# rpiSensors.net
KiCad netlist of a schematic drawn in EAGLE
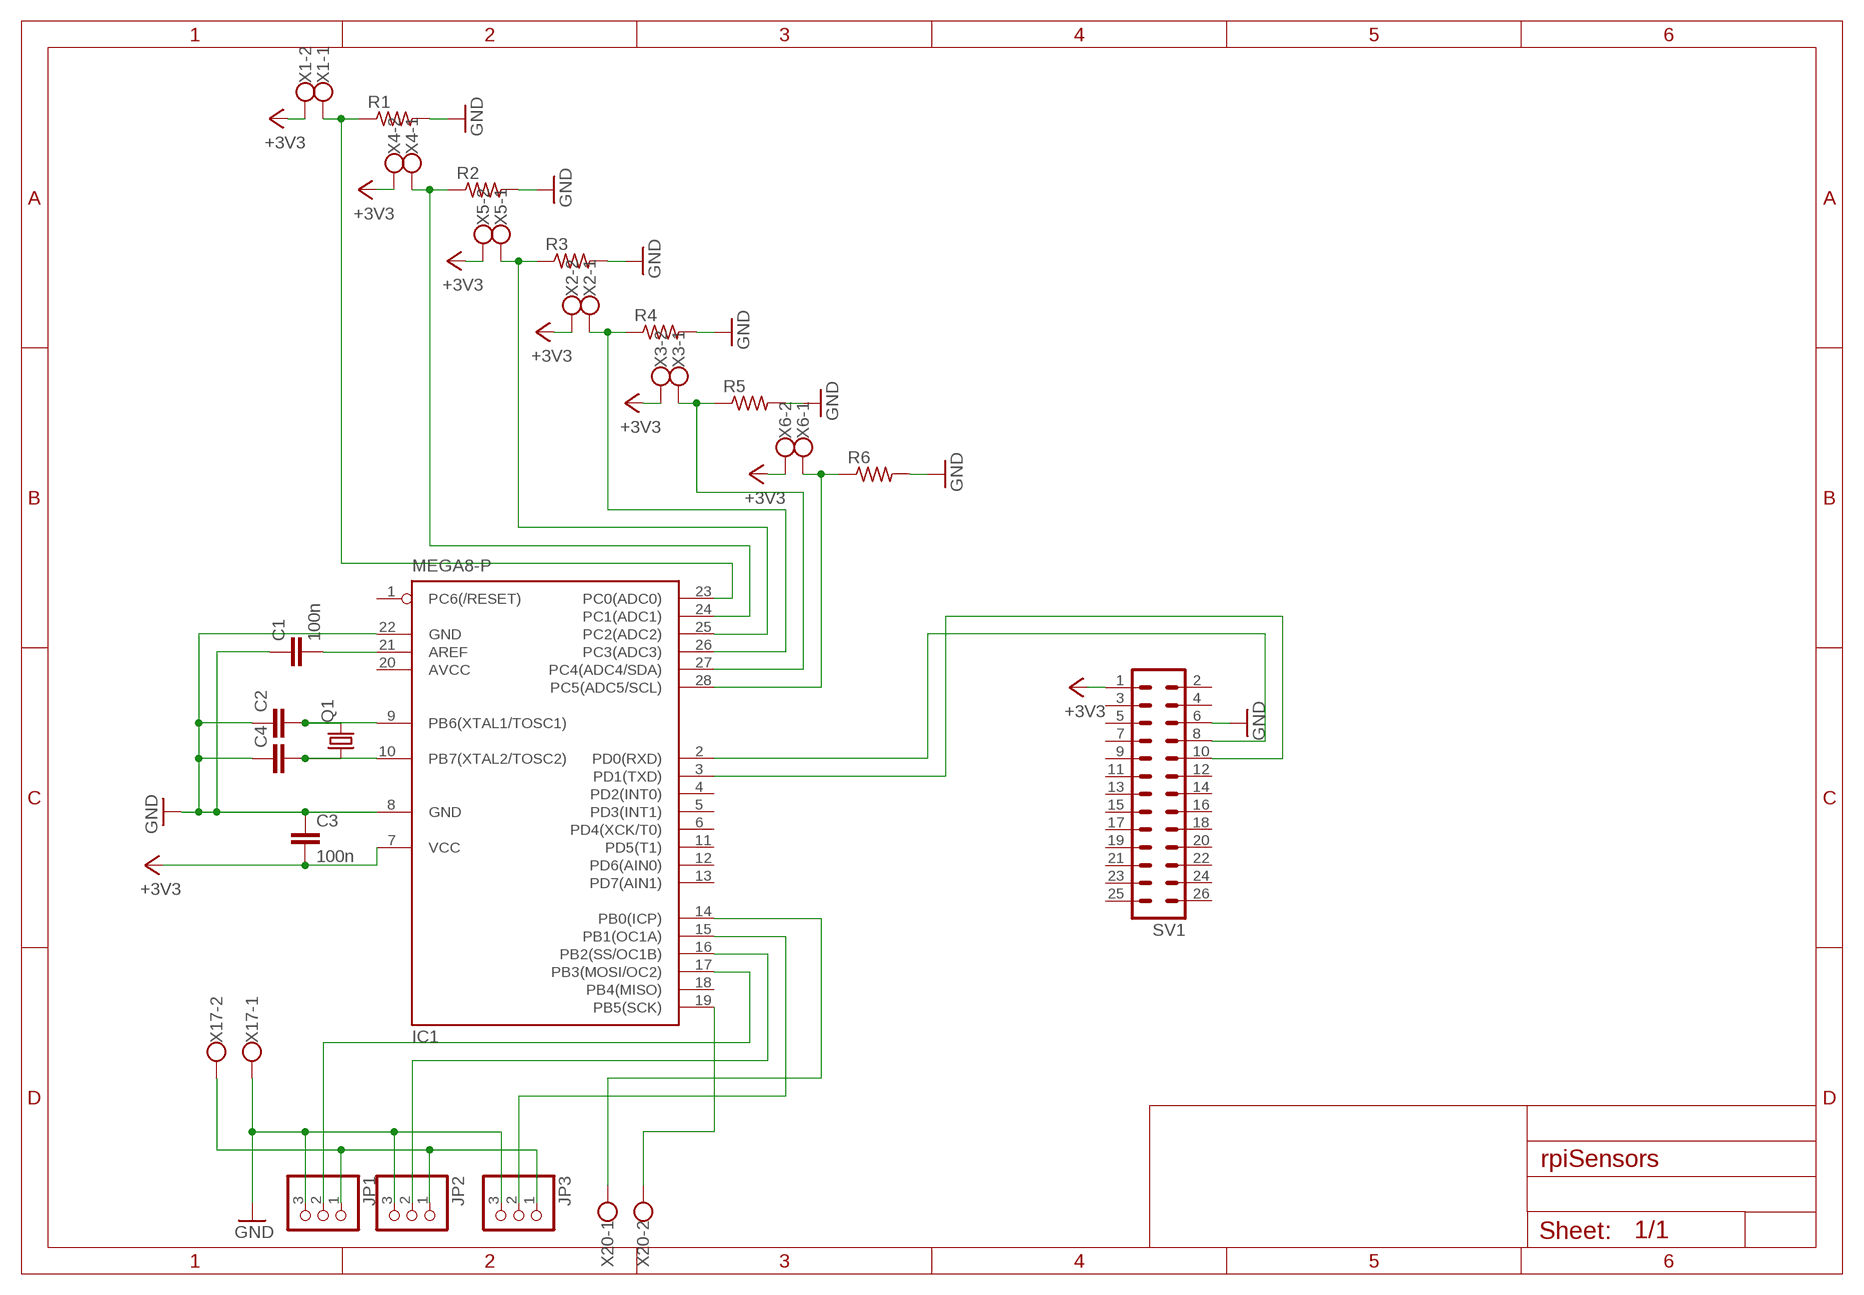
[diagram p0: schematic, sheet 1]

(export (version "E")
  (design (tool "Eeschema 10.0.6"))
  (components
    (comp (ref "C1")
      (value "100n")
      (footprint "eagle-import:C2.5-3")
      (libsource (lib "eagle-import") (part "C2,5-3"))
    )
    (comp (ref "C2")
      (value "C5/2.5")
      (footprint "eagle-import:C5B2.5")
      (libsource (lib "eagle-import") (part "C5/2.5"))
    )
    (comp (ref "C3")
      (value "100n")
      (footprint "eagle-import:C2.5-3")
      (libsource (lib "eagle-import") (part "C2,5-3"))
    )
    (comp (ref "C4")
      (value "C5/2.5")
      (footprint "eagle-import:C5B2.5")
      (libsource (lib "eagle-import") (part "C5/2.5"))
    )
    (comp (ref "IC1")
      (value "MEGA8-P")
      (footprint "eagle-import:DIL28-3")
      (libsource (lib "eagle-import") (part "MEGA8-P"))
    )
    (comp (ref "JP1")
      (value "PINHD-1X3")
      (footprint "eagle-import:1X03")
      (libsource (lib "eagle-import") (part "PINHD-1X3"))
    )
    (comp (ref "JP2")
      (value "PINHD-1X3")
      (footprint "eagle-import:1X03")
      (libsource (lib "eagle-import") (part "PINHD-1X3"))
    )
    (comp (ref "JP3")
      (value "PINHD-1X3")
      (footprint "eagle-import:1X03")
      (libsource (lib "eagle-import") (part "PINHD-1X3"))
    )
    (comp (ref "Q1")
      (value "CRYSTALHC49S")
      (footprint "eagle-import:HC49_S")
      (libsource (lib "eagle-import") (part "CRYSTALHC49S"))
    )
    (comp (ref "R1")
      (value "R-US_0309/12")
      (footprint "eagle-import:0309_12")
      (libsource (lib "eagle-import") (part "R-US_0309/12"))
    )
    (comp (ref "R2")
      (value "R-US_0309/12")
      (footprint "eagle-import:0309_12")
      (libsource (lib "eagle-import") (part "R-US_0309/12"))
    )
    (comp (ref "R3")
      (value "R-US_0309/12")
      (footprint "eagle-import:0309_12")
      (libsource (lib "eagle-import") (part "R-US_0309/12"))
    )
    (comp (ref "R4")
      (value "R-US_0309/12")
      (footprint "eagle-import:0309_12")
      (libsource (lib "eagle-import") (part "R-US_0309/12"))
    )
    (comp (ref "R5")
      (value "R-US_0309/12")
      (footprint "eagle-import:0309_12")
      (libsource (lib "eagle-import") (part "R-US_0309/12"))
    )
    (comp (ref "R6")
      (value "R-US_0309/12")
      (footprint "eagle-import:0309_12")
      (libsource (lib "eagle-import") (part "R-US_0309/12"))
    )
    (comp (ref "SV1")
      (value "ML26")
      (footprint "eagle-import:ML26")
      (libsource (lib "eagle-import") (part "ML26"))
    )
    (comp (ref "X1")
      (value "W237-102")
      (footprint "eagle-import:W237-102")
      (fields (field (name "MPN") "237-102"))
      (libsource (lib "eagle-import") (part "W237-102"))
    )
    (comp (ref "X2")
      (value "W237-102")
      (footprint "eagle-import:W237-102")
      (fields (field (name "MPN") "237-102"))
      (libsource (lib "eagle-import") (part "W237-102"))
    )
    (comp (ref "X3")
      (value "W237-102")
      (footprint "eagle-import:W237-102")
      (fields (field (name "MPN") "237-102"))
      (libsource (lib "eagle-import") (part "W237-102"))
    )
    (comp (ref "X4")
      (value "W237-102")
      (footprint "eagle-import:W237-102")
      (fields (field (name "MPN") "237-102"))
      (libsource (lib "eagle-import") (part "W237-102"))
    )
    (comp (ref "X5")
      (value "W237-102")
      (footprint "eagle-import:W237-102")
      (fields (field (name "MPN") "237-102"))
      (libsource (lib "eagle-import") (part "W237-102"))
    )
    (comp (ref "X6")
      (value "W237-102")
      (footprint "eagle-import:W237-102")
      (fields (field (name "MPN") "237-102"))
      (libsource (lib "eagle-import") (part "W237-102"))
    )
    (comp (ref "X17")
      (value "W237-102")
      (footprint "eagle-import:W237-102")
      (fields (field (name "MPN") "237-102"))
      (libsource (lib "eagle-import") (part "W237-102"))
    )
    (comp (ref "X20")
      (value "W237-102")
      (footprint "eagle-import:W237-102")
      (fields (field (name "MPN") "237-102"))
      (libsource (lib "eagle-import") (part "W237-102"))
    )
  )
  (nets
    (net (code "1") (name "+3V3") (class "Default")
      (node (ref "C3") (pin "2") (pinfunction "2_2") (pintype "passive"))
      (node (ref "IC1") (pin "7") (pinfunction "VCC_7") (pintype "power_in"))
      (node (ref "SV1") (pin "1") (pinfunction "1_1") (pintype "passive"))
      (node (ref "X1") (pin "2") (pinfunction "KL_2") (pintype "passive"))
      (node (ref "X2") (pin "2") (pinfunction "KL_2") (pintype "passive"))
      (node (ref "X3") (pin "2") (pinfunction "KL_2") (pintype "passive"))
      (node (ref "X4") (pin "2") (pinfunction "KL_2") (pintype "passive"))
      (node (ref "X5") (pin "2") (pinfunction "KL_2") (pintype "passive"))
      (node (ref "X6") (pin "2") (pinfunction "KL_2") (pintype "passive"))
    )
    (net (code "2") (name "/AVCC") (class "Default")
      (node (ref "IC1") (pin "20") (pinfunction "AVCC_20") (pintype "power_in"))
    )
    (net (code "3") (name "GND") (class "Default")
      (node (ref "C1") (pin "1") (pinfunction "1_1") (pintype "passive"))
      (node (ref "C2") (pin "1") (pinfunction "1_1") (pintype "passive"))
      (node (ref "C3") (pin "1") (pinfunction "1_1") (pintype "passive"))
      (node (ref "C4") (pin "1") (pinfunction "1_1") (pintype "passive"))
      (node (ref "IC1") (pin "22") (pinfunction "GND_22") (pintype "power_in"))
      (node (ref "IC1") (pin "8") (pinfunction "GND_8") (pintype "power_in"))
      (node (ref "JP1") (pin "3") (pinfunction "3_3") (pintype "passive"))
      (node (ref "JP2") (pin "3") (pinfunction "3_3") (pintype "passive"))
      (node (ref "JP3") (pin "3") (pinfunction "3_3") (pintype "passive"))
      (node (ref "R1") (pin "2") (pinfunction "2_2") (pintype "passive"))
      (node (ref "R2") (pin "2") (pinfunction "2_2") (pintype "passive"))
      (node (ref "R3") (pin "2") (pinfunction "2_2") (pintype "passive"))
      (node (ref "R4") (pin "2") (pinfunction "2_2") (pintype "passive"))
      (node (ref "R5") (pin "2") (pinfunction "2_2") (pintype "passive"))
      (node (ref "R6") (pin "2") (pinfunction "2_2") (pintype "passive"))
      (node (ref "SV1") (pin "6") (pinfunction "6_6") (pintype "passive"))
      (node (ref "X17") (pin "1") (pinfunction "KL_1") (pintype "passive"))
    )
    (net (code "4") (name "Net-(IC1-AREF)") (class "Default")
      (node (ref "C1") (pin "2") (pinfunction "2_2") (pintype "passive"))
      (node (ref "IC1") (pin "21") (pinfunction "AREF_21") (pintype "passive"))
    )
    (net (code "5") (name "Net-(IC1-PB0(ICP))") (class "Default")
      (node (ref "IC1") (pin "14") (pinfunction "PB0(ICP)_14") (pintype "bidirectional"))
      (node (ref "X20") (pin "1") (pinfunction "KL_1") (pintype "passive"))
    )
    (net (code "6") (name "Net-(IC1-PB1(OC1A))") (class "Default")
      (node (ref "IC1") (pin "15") (pinfunction "PB1(OC1A)_15") (pintype "bidirectional"))
      (node (ref "JP3") (pin "2") (pinfunction "2_2") (pintype "passive"))
    )
    (net (code "7") (name "Net-(IC1-PB2(SS{slash}OC1B))") (class "Default")
      (node (ref "IC1") (pin "16") (pinfunction "PB2(SS/OC1B)_16") (pintype "bidirectional"))
      (node (ref "JP2") (pin "2") (pinfunction "2_2") (pintype "passive"))
    )
    (net (code "8") (name "Net-(IC1-PB3(MOSI{slash}OC2))") (class "Default")
      (node (ref "IC1") (pin "17") (pinfunction "PB3(MOSI/OC2)_17") (pintype "bidirectional"))
      (node (ref "JP1") (pin "2") (pinfunction "2_2") (pintype "passive"))
    )
    (net (code "9") (name "Net-(IC1-PB5(SCK))") (class "Default")
      (node (ref "IC1") (pin "19") (pinfunction "PB5(SCK)_19") (pintype "bidirectional"))
      (node (ref "X20") (pin "2") (pinfunction "KL_2") (pintype "passive"))
    )
    (net (code "10") (name "Net-(IC1-PB6(XTAL1{slash}TOSC1))") (class "Default")
      (node (ref "C2") (pin "2") (pinfunction "2_2") (pintype "passive"))
      (node (ref "IC1") (pin "9") (pinfunction "PB6(XTAL1/TOSC1)_9") (pintype "bidirectional"))
      (node (ref "Q1") (pin "2") (pinfunction "2_2") (pintype "passive"))
    )
    (net (code "11") (name "Net-(IC1-PB7(XTAL2{slash}TOSC2))") (class "Default")
      (node (ref "C4") (pin "2") (pinfunction "2_2") (pintype "passive"))
      (node (ref "IC1") (pin "10") (pinfunction "PB7(XTAL2/TOSC2)_10") (pintype "bidirectional"))
      (node (ref "Q1") (pin "1") (pinfunction "1_1") (pintype "passive"))
    )
    (net (code "12") (name "Net-(IC1-PC0(ADC0))") (class "Default")
      (node (ref "IC1") (pin "23") (pinfunction "PC0(ADC0)_23") (pintype "bidirectional"))
      (node (ref "R1") (pin "1") (pinfunction "1_1") (pintype "passive"))
      (node (ref "X1") (pin "1") (pinfunction "KL_1") (pintype "passive"))
    )
    (net (code "13") (name "Net-(IC1-PC1(ADC1))") (class "Default")
      (node (ref "IC1") (pin "24") (pinfunction "PC1(ADC1)_24") (pintype "bidirectional"))
      (node (ref "R2") (pin "1") (pinfunction "1_1") (pintype "passive"))
      (node (ref "X4") (pin "1") (pinfunction "KL_1") (pintype "passive"))
    )
    (net (code "14") (name "Net-(IC1-PC2(ADC2))") (class "Default")
      (node (ref "IC1") (pin "25") (pinfunction "PC2(ADC2)_25") (pintype "bidirectional"))
      (node (ref "R3") (pin "1") (pinfunction "1_1") (pintype "passive"))
      (node (ref "X5") (pin "1") (pinfunction "KL_1") (pintype "passive"))
    )
    (net (code "15") (name "Net-(IC1-PC3(ADC3))") (class "Default")
      (node (ref "IC1") (pin "26") (pinfunction "PC3(ADC3)_26") (pintype "bidirectional"))
      (node (ref "R4") (pin "1") (pinfunction "1_1") (pintype "passive"))
      (node (ref "X2") (pin "1") (pinfunction "KL_1") (pintype "passive"))
    )
    (net (code "16") (name "Net-(IC1-PC4(ADC4{slash}SDA))") (class "Default")
      (node (ref "IC1") (pin "27") (pinfunction "PC4(ADC4/SDA)_27") (pintype "bidirectional"))
      (node (ref "R5") (pin "1") (pinfunction "1_1") (pintype "passive"))
      (node (ref "X3") (pin "1") (pinfunction "KL_1") (pintype "passive"))
    )
    (net (code "17") (name "Net-(IC1-PC5(ADC5{slash}SCL))") (class "Default")
      (node (ref "IC1") (pin "28") (pinfunction "PC5(ADC5/SCL)_28") (pintype "bidirectional"))
      (node (ref "R6") (pin "1") (pinfunction "1_1") (pintype "passive"))
      (node (ref "X6") (pin "1") (pinfunction "KL_1") (pintype "passive"))
    )
    (net (code "18") (name "Net-(IC1-PD0(RXD))") (class "Default")
      (node (ref "IC1") (pin "2") (pinfunction "PD0(RXD)_2") (pintype "bidirectional"))
      (node (ref "SV1") (pin "8") (pinfunction "8_8") (pintype "passive"))
    )
    (net (code "19") (name "Net-(IC1-PD1(TXD))") (class "Default")
      (node (ref "IC1") (pin "3") (pinfunction "PD1(TXD)_3") (pintype "bidirectional"))
      (node (ref "SV1") (pin "10") (pinfunction "10_10") (pintype "passive"))
    )
    (net (code "20") (name "Net-(X17B-KL)") (class "Default")
      (node (ref "JP1") (pin "1") (pinfunction "1_1") (pintype "passive"))
      (node (ref "JP2") (pin "1") (pinfunction "1_1") (pintype "passive"))
      (node (ref "JP3") (pin "1") (pinfunction "1_1") (pintype "passive"))
      (node (ref "X17") (pin "2") (pinfunction "KL_2") (pintype "passive"))
    )
    (net (code "21") (name "unconnected-(IC1-PB4(MISO)-Pad18)") (class "Default")
      (node (ref "IC1") (pin "18") (pinfunction "PB4(MISO)_18") (pintype "bidirectional"))
    )
    (net (code "22") (name "unconnected-(IC1-PC6({slash}RESET)-Pad1)") (class "Default")
      (node (ref "IC1") (pin "1") (pinfunction "PC6(/RESET)_1") (pintype "bidirectional"))
    )
    (net (code "23") (name "unconnected-(IC1-PD2(INT0)-Pad4)") (class "Default")
      (node (ref "IC1") (pin "4") (pinfunction "PD2(INT0)_4") (pintype "bidirectional"))
    )
    (net (code "24") (name "unconnected-(IC1-PD3(INT1)-Pad5)") (class "Default")
      (node (ref "IC1") (pin "5") (pinfunction "PD3(INT1)_5") (pintype "bidirectional"))
    )
    (net (code "25") (name "unconnected-(IC1-PD4(XCK{slash}T0)-Pad6)") (class "Default")
      (node (ref "IC1") (pin "6") (pinfunction "PD4(XCK/T0)_6") (pintype "bidirectional"))
    )
    (net (code "26") (name "unconnected-(IC1-PD5(T1)-Pad11)") (class "Default")
      (node (ref "IC1") (pin "11") (pinfunction "PD5(T1)_11") (pintype "bidirectional"))
    )
    (net (code "27") (name "unconnected-(IC1-PD6(AIN0)-Pad12)") (class "Default")
      (node (ref "IC1") (pin "12") (pinfunction "PD6(AIN0)_12") (pintype "bidirectional"))
    )
    (net (code "28") (name "unconnected-(IC1-PD7(AIN1)-Pad13)") (class "Default")
      (node (ref "IC1") (pin "13") (pinfunction "PD7(AIN1)_13") (pintype "bidirectional"))
    )
    (net (code "29") (name "unconnected-(SV1-Pad2)") (class "Default")
      (node (ref "SV1") (pin "2") (pinfunction "2_2") (pintype "passive"))
    )
    (net (code "30") (name "unconnected-(SV1-Pad3)") (class "Default")
      (node (ref "SV1") (pin "3") (pinfunction "3_3") (pintype "passive"))
    )
    (net (code "31") (name "unconnected-(SV1-Pad4)") (class "Default")
      (node (ref "SV1") (pin "4") (pinfunction "4_4") (pintype "passive"))
    )
    (net (code "32") (name "unconnected-(SV1-Pad5)") (class "Default")
      (node (ref "SV1") (pin "5") (pinfunction "5_5") (pintype "passive"))
    )
    (net (code "33") (name "unconnected-(SV1-Pad7)") (class "Default")
      (node (ref "SV1") (pin "7") (pinfunction "7_7") (pintype "passive"))
    )
    (net (code "34") (name "unconnected-(SV1-Pad9)") (class "Default")
      (node (ref "SV1") (pin "9") (pinfunction "9_9") (pintype "passive"))
    )
    (net (code "35") (name "unconnected-(SV1-Pad11)") (class "Default")
      (node (ref "SV1") (pin "11") (pinfunction "11_11") (pintype "passive"))
    )
    (net (code "36") (name "unconnected-(SV1-Pad12)") (class "Default")
      (node (ref "SV1") (pin "12") (pinfunction "12_12") (pintype "passive"))
    )
    (net (code "37") (name "unconnected-(SV1-Pad13)") (class "Default")
      (node (ref "SV1") (pin "13") (pinfunction "13_13") (pintype "passive"))
    )
    (net (code "38") (name "unconnected-(SV1-Pad14)") (class "Default")
      (node (ref "SV1") (pin "14") (pinfunction "14_14") (pintype "passive"))
    )
    (net (code "39") (name "unconnected-(SV1-Pad15)") (class "Default")
      (node (ref "SV1") (pin "15") (pinfunction "15_15") (pintype "passive"))
    )
    (net (code "40") (name "unconnected-(SV1-Pad16)") (class "Default")
      (node (ref "SV1") (pin "16") (pinfunction "16_16") (pintype "passive"))
    )
    (net (code "41") (name "unconnected-(SV1-Pad17)") (class "Default")
      (node (ref "SV1") (pin "17") (pinfunction "17_17") (pintype "passive"))
    )
    (net (code "42") (name "unconnected-(SV1-Pad18)") (class "Default")
      (node (ref "SV1") (pin "18") (pinfunction "18_18") (pintype "passive"))
    )
    (net (code "43") (name "unconnected-(SV1-Pad19)") (class "Default")
      (node (ref "SV1") (pin "19") (pinfunction "19_19") (pintype "passive"))
    )
    (net (code "44") (name "unconnected-(SV1-Pad20)") (class "Default")
      (node (ref "SV1") (pin "20") (pinfunction "20_20") (pintype "passive"))
    )
    (net (code "45") (name "unconnected-(SV1-Pad21)") (class "Default")
      (node (ref "SV1") (pin "21") (pinfunction "21_21") (pintype "passive"))
    )
    (net (code "46") (name "unconnected-(SV1-Pad22)") (class "Default")
      (node (ref "SV1") (pin "22") (pinfunction "22_22") (pintype "passive"))
    )
    (net (code "47") (name "unconnected-(SV1-Pad23)") (class "Default")
      (node (ref "SV1") (pin "23") (pinfunction "23_23") (pintype "passive"))
    )
    (net (code "48") (name "unconnected-(SV1-Pad24)") (class "Default")
      (node (ref "SV1") (pin "24") (pinfunction "24_24") (pintype "passive"))
    )
    (net (code "49") (name "unconnected-(SV1-Pad25)") (class "Default")
      (node (ref "SV1") (pin "25") (pinfunction "25_25") (pintype "passive"))
    )
    (net (code "50") (name "unconnected-(SV1-Pad26)") (class "Default")
      (node (ref "SV1") (pin "26") (pinfunction "26_26") (pintype "passive"))
    )
  )
)
